# Input_channel.net
KiCad netlist of a schematic drawn in Altium Designer
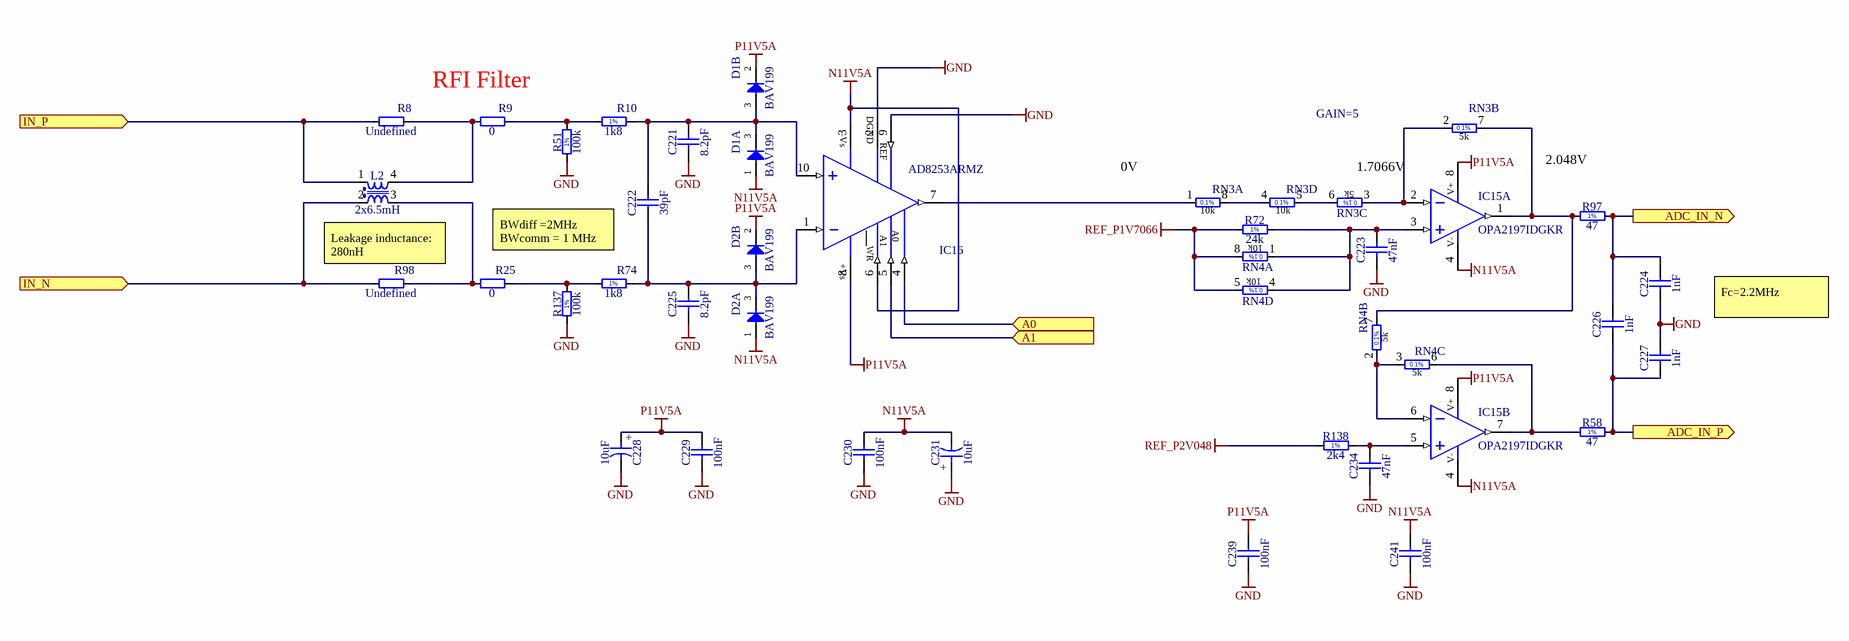
[diagram p0: Input_channel.SchDoc]

(export (version "E")
  (design (tool "Eeschema 10.0.6"))
  (components
    (comp (ref "C221")
      (value "8.2pF")
      (footprint "CAPC1608X87N")
      (description "Non-polarised capacitor")
      (fields
        (field (name "PART NUMBER") "CC0603_8.2PF_50V_0.5PF_NP0")
        (field (name "VOLTAGE") "50V")
        (field (name "AUTHOR") "CERN DEM JLC")
      )
      (libsource (lib "Capacitors") (part "Capacitor - non polarized"))
    )
    (comp (ref "C222")
      (value "39pF")
      (footprint "CAPC1608X87N")
      (description "Non-polarised capacitor")
      (fields
        (field (name "PART NUMBER") "CC0603_39PF_50V_5%_NP0")
        (field (name "VOLTAGE") "50V")
        (field (name "AUTHOR") "CERN DEM JLC")
      )
      (libsource (lib "Capacitors") (part "Capacitor - non polarized"))
    )
    (comp (ref "C223")
      (value "47nF")
      (footprint "CAPC2012X135N")
      (description "Non-polarised capacitor")
      (fields
        (field (name "PART NUMBER") "CC0805_47NF_25V_5%_C0G")
        (field (name "VOLTAGE") "25V")
        (field (name "AUTHOR") "CERN DEM JLC")
      )
      (libsource (lib "Capacitors") (part "Capacitor - non polarized"))
    )
    (comp (ref "C224")
      (value "1nF")
      (footprint "CAPC1608X90N")
      (description "Non-polarised capacitor")
      (fields
        (field (name "PART NUMBER") "CC0603_1NF_50V_1%_NP0")
        (field (name "VOLTAGE") "50V")
        (field (name "AUTHOR") "CERN DEM JLC")
      )
      (libsource (lib "Capacitors") (part "Capacitor - non polarized"))
    )
    (comp (ref "C225")
      (value "8.2pF")
      (footprint "CAPC1608X87N")
      (description "Non-polarised capacitor")
      (fields
        (field (name "PART NUMBER") "CC0603_8.2PF_50V_0.5PF_NP0")
        (field (name "VOLTAGE") "50V")
        (field (name "AUTHOR") "CERN DEM JLC")
      )
      (libsource (lib "Capacitors") (part "Capacitor - non polarized"))
    )
    (comp (ref "C226")
      (value "1nF")
      (footprint "CAPC1608X90N")
      (description "Non-polarised capacitor")
      (fields
        (field (name "PART NUMBER") "CC0603_1NF_50V_1%_NP0")
        (field (name "VOLTAGE") "50V")
        (field (name "AUTHOR") "CERN DEM JLC")
      )
      (libsource (lib "Capacitors") (part "Capacitor - non polarized"))
    )
    (comp (ref "C227")
      (value "1nF")
      (footprint "CAPC1608X90N")
      (description "Non-polarised capacitor")
      (fields
        (field (name "PART NUMBER") "CC0603_1NF_50V_1%_NP0")
        (field (name "VOLTAGE") "50V")
        (field (name "AUTHOR") "CERN DEM JLC")
      )
      (libsource (lib "Capacitors") (part "Capacitor - non polarized"))
    )
    (comp (ref "C228")
      (value "10uF")
      (footprint "CAPMP3216X180N")
      (description "Polarised capacitor")
      (fields
        (field (name "PART NUMBER") "CTE3216-18_10UF_16V_20%_AVX_TCJ")
        (field (name "VOLTAGE") "16V")
        (field (name "AUTHOR") "CERN DEM JLC")
      )
      (libsource (lib "Capacitors") (part "Capacitor - polarized"))
    )
    (comp (ref "C229")
      (value "100nF")
      (footprint "CAPC1005X55N")
      (description "Non-polarised capacitor")
      (fields
        (field (name "PART NUMBER") "CC0402_100NF_16V_10%_X7R")
        (field (name "VOLTAGE") "16V")
        (field (name "AUTHOR") "CERN DEM JLC")
      )
      (libsource (lib "Capacitors") (part "Capacitor - non polarized"))
    )
    (comp (ref "C230")
      (value "100nF")
      (footprint "CAPC1005X55N")
      (description "Non-polarised capacitor")
      (fields
        (field (name "PART NUMBER") "CC0402_100NF_16V_10%_X7R")
        (field (name "VOLTAGE") "16V")
        (field (name "AUTHOR") "CERN DEM JLC")
      )
      (libsource (lib "Capacitors") (part "Capacitor - non polarized"))
    )
    (comp (ref "C231")
      (value "10uF")
      (footprint "CAPMP3216X180N")
      (description "Polarised capacitor")
      (fields
        (field (name "PART NUMBER") "CTE3216-18_10UF_16V_20%_AVX_TCJ")
        (field (name "VOLTAGE") "16V")
        (field (name "AUTHOR") "CERN DEM JLC")
      )
      (libsource (lib "Capacitors") (part "Capacitor - polarized"))
    )
    (comp (ref "C234")
      (value "47nF")
      (footprint "CAPC2012X135N")
      (description "Non-polarised capacitor")
      (fields
        (field (name "PART NUMBER") "CC0805_47NF_25V_5%_C0G")
        (field (name "VOLTAGE") "25V")
        (field (name "AUTHOR") "CERN DEM JLC")
      )
      (libsource (lib "Capacitors") (part "Capacitor - non polarized"))
    )
    (comp (ref "C239")
      (value "100nF")
      (footprint "CAPC1005X55N")
      (description "Non-polarised capacitor")
      (fields
        (field (name "PART NUMBER") "CC0402_100NF_16V_10%_X7R")
        (field (name "VOLTAGE") "16V")
        (field (name "AUTHOR") "CERN DEM JLC")
      )
      (libsource (lib "Capacitors") (part "Capacitor - non polarized"))
    )
    (comp (ref "C241")
      (value "100nF")
      (footprint "CAPC1005X55N")
      (description "Non-polarised capacitor")
      (fields
        (field (name "PART NUMBER") "CC0402_100NF_16V_10%_X7R")
        (field (name "VOLTAGE") "16V")
        (field (name "AUTHOR") "CERN DEM JLC")
      )
      (libsource (lib "Capacitors") (part "Capacitor - non polarized"))
    )
    (comp (ref "D1")
      (value "BAV199")
      (footprint "SOT95P240X110-3N")
      (description "Serial Diode")
      (fields
        (field (name "VOLTAGE") "75V")
        (field (name "POWER") "250mW")
        (field (name "AUTHOR") "CERN DEM JMW")
      )
      (libsource (lib "ICs And Semiconductors") (part "Diode x2 A1C3_A3C2"))
    )
    (comp (ref "D2")
      (value "BAV199")
      (footprint "SOT95P240X110-3N")
      (description "Serial Diode")
      (fields
        (field (name "VOLTAGE") "75V")
        (field (name "POWER") "250mW")
        (field (name "AUTHOR") "CERN DEM JMW")
      )
      (libsource (lib "ICs And Semiconductors") (part "Diode x2 A1C3_A3C2"))
    )
    (comp (ref "IC15")
      (value "OPA2197IDGKR")
      (footprint "SOP65P490X110-8N")
      (description "36-V, Precision, Rail-to-Rail Input Output, Low Offset Voltage Op Amp 8-VSSOP")
      (fields (field (name "MANUFACTURER") "TEXAS INSTRUMENTS") (field (name "AUTHOR") "GK"))
      (libsource (lib "LIBRARY_SCH") (part "OA_OPA2197IDGKR"))
    )
    (comp (ref "IC16")
      (value "AD8253ARMZ")
      (footprint "SOP50P490X110-10N")
      (description "10MHz, 20V/us, G= 1, 10, 100, 1000 iCMOS Programmable Gain Instrumentation Amplifier")
      (fields (field (name "MANUFACTURER") "ANALOG DEVICES") (field (name "AUTHOR") "CERN DEM JLC"))
      (libsource (lib "ICs And Semiconductors") (part "AD8253"))
    )
    (comp (ref "L2")
      (value "2x6.5mH")
      (footprint "IND_WURTH_WE-SL2")
      (description "Inductor Common Mode")
      (fields
        (field (name "PART NUMBER") "IND_6.5MH_50%_WURTH_WE-SL2-744229")
        (field (name "POWER") "400mA")
        (field (name "AUTHOR") "CERN DEM JLC")
      )
      (libsource (lib "Inductors & Transformers") (part "Inductor Common Mode 1Dot-4 2Dot-3"))
    )
    (comp (ref "R8")
      (value "Undefined")
      (footprint "RESC1608X55N")
      (description "Resistor")
      (fields (field (name "PART NUMBER") "R0603_NO-VALUE") (field (name "AUTHOR") "CERN DEM JLC"))
      (libsource (lib "Resistors") (part "Resistor"))
    )
    (comp (ref "R9")
      (value "0")
      (footprint "RESC1608X55N")
      (description "Resistor")
      (fields
        (field (name "PART NUMBER") "R0603_0R_JUMPER")
        (field (name "MANUFACTURER") "GENERIC")
        (field (name "AUTHOR") "CERN DEM JLC")
      )
      (libsource (lib "Resistors") (part "Resistor"))
    )
    (comp (ref "R10")
      (value "1k8")
      (footprint "RESC1608X55N")
      (description "Resistor - 1%")
      (fields
        (field (name "PART NUMBER") "R0603_1K8_1%_0.1W_100PPM")
        (field (name "POWER") "0.1W")
        (field (name "AUTHOR") "CERN DEM JLC")
      )
      (libsource (lib "Resistors") (part "Resistor - 1%"))
    )
    (comp (ref "R25")
      (value "0")
      (footprint "RESC1608X55N")
      (description "Resistor")
      (fields
        (field (name "PART NUMBER") "R0603_0R_JUMPER")
        (field (name "MANUFACTURER") "GENERIC")
        (field (name "AUTHOR") "CERN DEM JLC")
      )
      (libsource (lib "Resistors") (part "Resistor"))
    )
    (comp (ref "R51")
      (value "100k")
      (footprint "RESC1608X55N")
      (description "Resistor - 1%")
      (fields
        (field (name "PART NUMBER") "R0603_100K_1%_0.1W_100PPM")
        (field (name "POWER") "0.1W")
        (field (name "AUTHOR") "CERN DEM JLC")
      )
      (libsource (lib "Resistors") (part "Resistor - 1%"))
    )
    (comp (ref "R58")
      (value "47")
      (footprint "RESC1005X40N")
      (description "Resistor - 1%")
      (fields
        (field (name "PART NUMBER") "R0402_47R_1%_0.0625W_100PPM")
        (field (name "POWER") "0.0625W")
        (field (name "AUTHOR") "CERN DEM JLC")
      )
      (libsource (lib "Resistors") (part "Resistor - 1%"))
    )
    (comp (ref "R72")
      (value "24k")
      (footprint "RESC1608X55N")
      (description "Resistor - 1%")
      (fields
        (field (name "PART NUMBER") "R0603_24K_1%_0.1W_100PPM")
        (field (name "POWER") "0.1W")
        (field (name "AUTHOR") "CERN DEM JLC")
      )
      (libsource (lib "Resistors") (part "Resistor - 1%"))
    )
    (comp (ref "R74")
      (value "1k8")
      (footprint "RESC1608X55N")
      (description "Resistor - 1%")
      (fields
        (field (name "PART NUMBER") "R0603_1K8_1%_0.1W_100PPM")
        (field (name "POWER") "0.1W")
        (field (name "AUTHOR") "CERN DEM JLC")
      )
      (libsource (lib "Resistors") (part "Resistor - 1%"))
    )
    (comp (ref "R97")
      (value "47")
      (footprint "RESC1005X40N")
      (description "Resistor - 1%")
      (fields
        (field (name "PART NUMBER") "R0402_47R_1%_0.0625W_100PPM")
        (field (name "POWER") "0.0625W")
        (field (name "AUTHOR") "CERN DEM JLC")
      )
      (libsource (lib "Resistors") (part "Resistor - 1%"))
    )
    (comp (ref "R98")
      (value "Undefined")
      (footprint "RESC1608X55N")
      (description "Resistor")
      (fields (field (name "PART NUMBER") "R0603_NO-VALUE") (field (name "AUTHOR") "CERN DEM JLC"))
      (libsource (lib "Resistors") (part "Resistor"))
    )
    (comp (ref "R137")
      (value "100k")
      (footprint "RESC1608X55N")
      (description "Resistor - 1%")
      (fields
        (field (name "PART NUMBER") "R0603_100K_1%_0.1W_100PPM")
        (field (name "POWER") "0.1W")
        (field (name "AUTHOR") "CERN DEM JLC")
      )
      (libsource (lib "Resistors") (part "Resistor - 1%"))
    )
    (comp (ref "R138")
      (value "2k4")
      (footprint "RESC1005X40N")
      (description "Resistor - 1%")
      (fields
        (field (name "PART NUMBER") "R0402_2K4_1%_0.0625W_100PPM")
        (field (name "POWER") "0.0625W")
        (field (name "AUTHOR") "CERN DEM JLC")
      )
      (libsource (lib "Resistors") (part "Resistor - 1%"))
    )
    (comp (ref "RN3")
      (value "10k 5K 5K 10K")
      (footprint "SOIC127P600X175-8N")
      (description "DIL8 Resistor Network 4 Resistors 10k-5k-5k-10k 0.1%")
      (fields
        (field (name "PART NUMBER") "RN_10K_5K_VISHAY_AORN2-1AT3")
        (field (name "POWER") "4x0.1W")
        (field (name "AUTHOR") "CERN DEM JLC")
      )
      (libsource (lib "Resistors") (part "RN DIL8_4xR_10k-5k-5k-10k_0.1%"))
    )
    (comp (ref "RN4")
      (value "10k 5K 5K 10K")
      (footprint "SOIC127P600X175-8N")
      (description "DIL8 Resistor Network 4 Resistors 10k-5k-5k-10k 0.1%")
      (fields
        (field (name "PART NUMBER") "RN_10K_5K_VISHAY_AORN2-1AT3")
        (field (name "POWER") "4x0.1W")
        (field (name "AUTHOR") "CERN DEM JLC")
      )
      (libsource (lib "Resistors") (part "RN DIL8_4xR_10k-5k-5k-10k_0.1%"))
    )
  )
  (nets
    (net (code "1") (name "/A0") (class "Default")
      (node (ref "IC16") (pin "4") (pinfunction "A0_4") (pintype "input"))
    )
    (net (code "2") (name "/A1") (class "Default")
      (node (ref "IC16") (pin "5") (pinfunction "A1_5") (pintype "input"))
    )
    (net (code "3") (name "/ADC_IN_N") (class "Default")
      (node (ref "C224") (pin "2") (pinfunction "2_2") (pintype "passive"))
      (node (ref "C226") (pin "2") (pinfunction "2_2") (pintype "passive"))
      (node (ref "R97") (pin "2") (pinfunction "2_2") (pintype "passive"))
    )
    (net (code "4") (name "/ADC_IN_P") (class "Default")
      (node (ref "C226") (pin "1") (pinfunction "1_1") (pintype "passive"))
      (node (ref "C227") (pin "1") (pinfunction "1_1") (pintype "passive"))
      (node (ref "R58") (pin "2") (pinfunction "2_2") (pintype "passive"))
    )
    (net (code "5") (name "/IN_N") (class "Default")
      (node (ref "L2") (pin "2") (pinfunction "2_2") (pintype "passive"))
      (node (ref "R98") (pin "1") (pinfunction "1_1") (pintype "passive"))
    )
    (net (code "6") (name "/IN_P") (class "Default")
      (node (ref "L2") (pin "1") (pinfunction "1_1") (pintype "passive"))
      (node (ref "R8") (pin "1") (pinfunction "1_1") (pintype "passive"))
    )
    (net (code "7") (name "GND") (class "Default")
      (node (ref "C221") (pin "1") (pinfunction "1_1") (pintype "passive"))
      (node (ref "C223") (pin "1") (pinfunction "1_1") (pintype "passive"))
      (node (ref "C224") (pin "1") (pinfunction "1_1") (pintype "passive"))
      (node (ref "C225") (pin "1") (pinfunction "1_1") (pintype "passive"))
      (node (ref "C227") (pin "2") (pinfunction "2_2") (pintype "passive"))
      (node (ref "C228") (pin "2") (pinfunction "2_2") (pintype "passive"))
      (node (ref "C229") (pin "1") (pinfunction "1_1") (pintype "passive"))
      (node (ref "C230") (pin "1") (pinfunction "1_1") (pintype "passive"))
      (node (ref "C231") (pin "1") (pinfunction "1_1") (pintype "passive"))
      (node (ref "C234") (pin "1") (pinfunction "1_1") (pintype "passive"))
      (node (ref "C239") (pin "1") (pinfunction "1_1") (pintype "passive"))
      (node (ref "C241") (pin "1") (pinfunction "1_1") (pintype "passive"))
      (node (ref "IC16") (pin "2") (pinfunction "DGND_2") (pintype "power_in"))
      (node (ref "IC16") (pin "9") (pinfunction "REF_9") (pintype "input"))
      (node (ref "R137") (pin "1") (pinfunction "1_1") (pintype "passive"))
      (node (ref "R51") (pin "1") (pinfunction "1_1") (pintype "passive"))
    )
    (net (code "8") (name "N11V5A") (class "Default")
      (node (ref "C230") (pin "2") (pinfunction "2_2") (pintype "passive"))
      (node (ref "C231") (pin "2") (pinfunction "2_2") (pintype "passive"))
      (node (ref "C241") (pin "2") (pinfunction "2_2") (pintype "passive"))
      (node (ref "D1") (pin "1") (pinfunction "A_1") (pintype "passive"))
      (node (ref "D2") (pin "1") (pinfunction "A_1") (pintype "passive"))
      (node (ref "IC15") (pin "4") (pinfunction "V-_4") (pintype "power_in"))
      (node (ref "IC16") (pin "3") (pinfunction "-VS_3") (pintype "power_in"))
      (node (ref "IC16") (pin "6") (pinfunction "~{WR}_6") (pintype "input"))
    )
    (net (code "9") (name "Net-(D1A-COMAC)") (class "Default")
      (node (ref "C221") (pin "2") (pinfunction "2_2") (pintype "passive"))
      (node (ref "C222") (pin "2") (pinfunction "2_2") (pintype "passive"))
      (node (ref "D1") (pin "3") (pinfunction "COMAC_3") (pintype "passive"))
      (node (ref "IC16") (pin "10") (pinfunction "+IN_10") (pintype "input"))
      (node (ref "R10") (pin "2") (pinfunction "2_2") (pintype "passive"))
    )
    (net (code "10") (name "Net-(D2A-COMAC)") (class "Default")
      (node (ref "C222") (pin "1") (pinfunction "1_1") (pintype "passive"))
      (node (ref "C225") (pin "2") (pinfunction "2_2") (pintype "passive"))
      (node (ref "D2") (pin "3") (pinfunction "COMAC_3") (pintype "passive"))
      (node (ref "IC16") (pin "1") (pinfunction "-IN_1") (pintype "input"))
      (node (ref "R74") (pin "2") (pinfunction "2_2") (pintype "passive"))
    )
    (net (code "11") (name "Net-(IC15A-IN+)") (class "Default")
      (node (ref "C223") (pin "2") (pinfunction "2_2") (pintype "passive"))
      (node (ref "IC15") (pin "3") (pinfunction "IN+_3") (pintype "input"))
      (node (ref "R72") (pin "2") (pinfunction "2_2") (pintype "passive"))
      (node (ref "RN4") (pin "1") (pinfunction "1_1") (pintype "passive"))
      (node (ref "RN4") (pin "4") (pinfunction "4_4") (pintype "passive"))
    )
    (net (code "12") (name "Net-(IC15A-IN-)") (class "Default")
      (node (ref "IC15") (pin "2") (pinfunction "IN-_2") (pintype "input"))
      (node (ref "RN3") (pin "2") (pinfunction "2_2") (pintype "passive"))
      (node (ref "RN3") (pin "3") (pinfunction "3_3") (pintype "passive"))
    )
    (net (code "13") (name "Net-(IC15A-OUT)") (class "Default")
      (node (ref "IC15") (pin "1") (pinfunction "OUT_1") (pintype "output"))
      (node (ref "R97") (pin "1") (pinfunction "1_1") (pintype "passive"))
      (node (ref "RN3") (pin "7") (pinfunction "7_7") (pintype "passive"))
      (node (ref "RN4") (pin "7") (pinfunction "7_7") (pintype "passive"))
    )
    (net (code "14") (name "Net-(IC15B-IN+)") (class "Default")
      (node (ref "C234") (pin "2") (pinfunction "2_2") (pintype "passive"))
      (node (ref "IC15") (pin "5") (pinfunction "IN+_5") (pintype "input"))
      (node (ref "R138") (pin "2") (pinfunction "2_2") (pintype "passive"))
    )
    (net (code "15") (name "Net-(IC15B-IN-)") (class "Default")
      (node (ref "IC15") (pin "6") (pinfunction "IN-_6") (pintype "input"))
      (node (ref "RN4") (pin "2") (pinfunction "2_2") (pintype "passive"))
      (node (ref "RN4") (pin "3") (pinfunction "3_3") (pintype "passive"))
    )
    (net (code "16") (name "Net-(IC15B-OUT)") (class "Default")
      (node (ref "IC15") (pin "7") (pinfunction "OUT_7") (pintype "output"))
      (node (ref "R58") (pin "1") (pinfunction "1_1") (pintype "passive"))
      (node (ref "RN4") (pin "6") (pinfunction "6_6") (pintype "passive"))
    )
    (net (code "17") (name "Net-(IC16-OUT)") (class "Default")
      (node (ref "IC16") (pin "7") (pinfunction "OUT_7") (pintype "output"))
      (node (ref "RN3") (pin "1") (pinfunction "1_1") (pintype "passive"))
    )
    (net (code "18") (name "Net-(L2-Pad3)") (class "Default")
      (node (ref "L2") (pin "3") (pinfunction "3_3") (pintype "passive"))
      (node (ref "R25") (pin "1") (pinfunction "1_1") (pintype "passive"))
      (node (ref "R98") (pin "2") (pinfunction "2_2") (pintype "passive"))
    )
    (net (code "19") (name "Net-(L2-Pad4)") (class "Default")
      (node (ref "L2") (pin "4") (pinfunction "4_4") (pintype "passive"))
      (node (ref "R8") (pin "2") (pinfunction "2_2") (pintype "passive"))
      (node (ref "R9") (pin "1") (pinfunction "1_1") (pintype "passive"))
    )
    (net (code "20") (name "Net-(R10-Pad1)") (class "Default")
      (node (ref "R10") (pin "1") (pinfunction "1_1") (pintype "passive"))
      (node (ref "R51") (pin "2") (pinfunction "2_2") (pintype "passive"))
      (node (ref "R9") (pin "2") (pinfunction "2_2") (pintype "passive"))
    )
    (net (code "21") (name "Net-(R137-Pad2)") (class "Default")
      (node (ref "R137") (pin "2") (pinfunction "2_2") (pintype "passive"))
      (node (ref "R25") (pin "2") (pinfunction "2_2") (pintype "passive"))
      (node (ref "R74") (pin "1") (pinfunction "1_1") (pintype "passive"))
    )
    (net (code "22") (name "Net-(RN3-Pad4)") (class "Default")
      (node (ref "RN3") (pin "4") (pinfunction "4_4") (pintype "passive"))
      (node (ref "RN3") (pin "8") (pinfunction "8_8") (pintype "passive"))
    )
    (net (code "23") (name "Net-(RN3-Pad5)") (class "Default")
      (node (ref "RN3") (pin "5") (pinfunction "5_5") (pintype "passive"))
      (node (ref "RN3") (pin "6") (pinfunction "6_6") (pintype "passive"))
    )
    (net (code "24") (name "P11V5A") (class "Default")
      (node (ref "C228") (pin "1") (pinfunction "1_1") (pintype "passive"))
      (node (ref "C229") (pin "2") (pinfunction "2_2") (pintype "passive"))
      (node (ref "C239") (pin "2") (pinfunction "2_2") (pintype "passive"))
      (node (ref "D1") (pin "2") (pinfunction "C_2") (pintype "passive"))
      (node (ref "D2") (pin "2") (pinfunction "C_2") (pintype "passive"))
      (node (ref "IC15") (pin "8") (pinfunction "V+_8") (pintype "power_in"))
      (node (ref "IC16") (pin "8") (pinfunction "+VS_8") (pintype "power_in"))
    )
    (net (code "25") (name "REF_P1V7066") (class "Default")
      (node (ref "R72") (pin "1") (pinfunction "1_1") (pintype "passive"))
      (node (ref "RN4") (pin "5") (pinfunction "5_5") (pintype "passive"))
      (node (ref "RN4") (pin "8") (pinfunction "8_8") (pintype "passive"))
    )
    (net (code "26") (name "REF_P2V048") (class "Default")
      (node (ref "R138") (pin "1") (pinfunction "1_1") (pintype "passive"))
    )
  )
)
